# Sheet2.net
KiCad netlist of a schematic drawn in Altium Designer
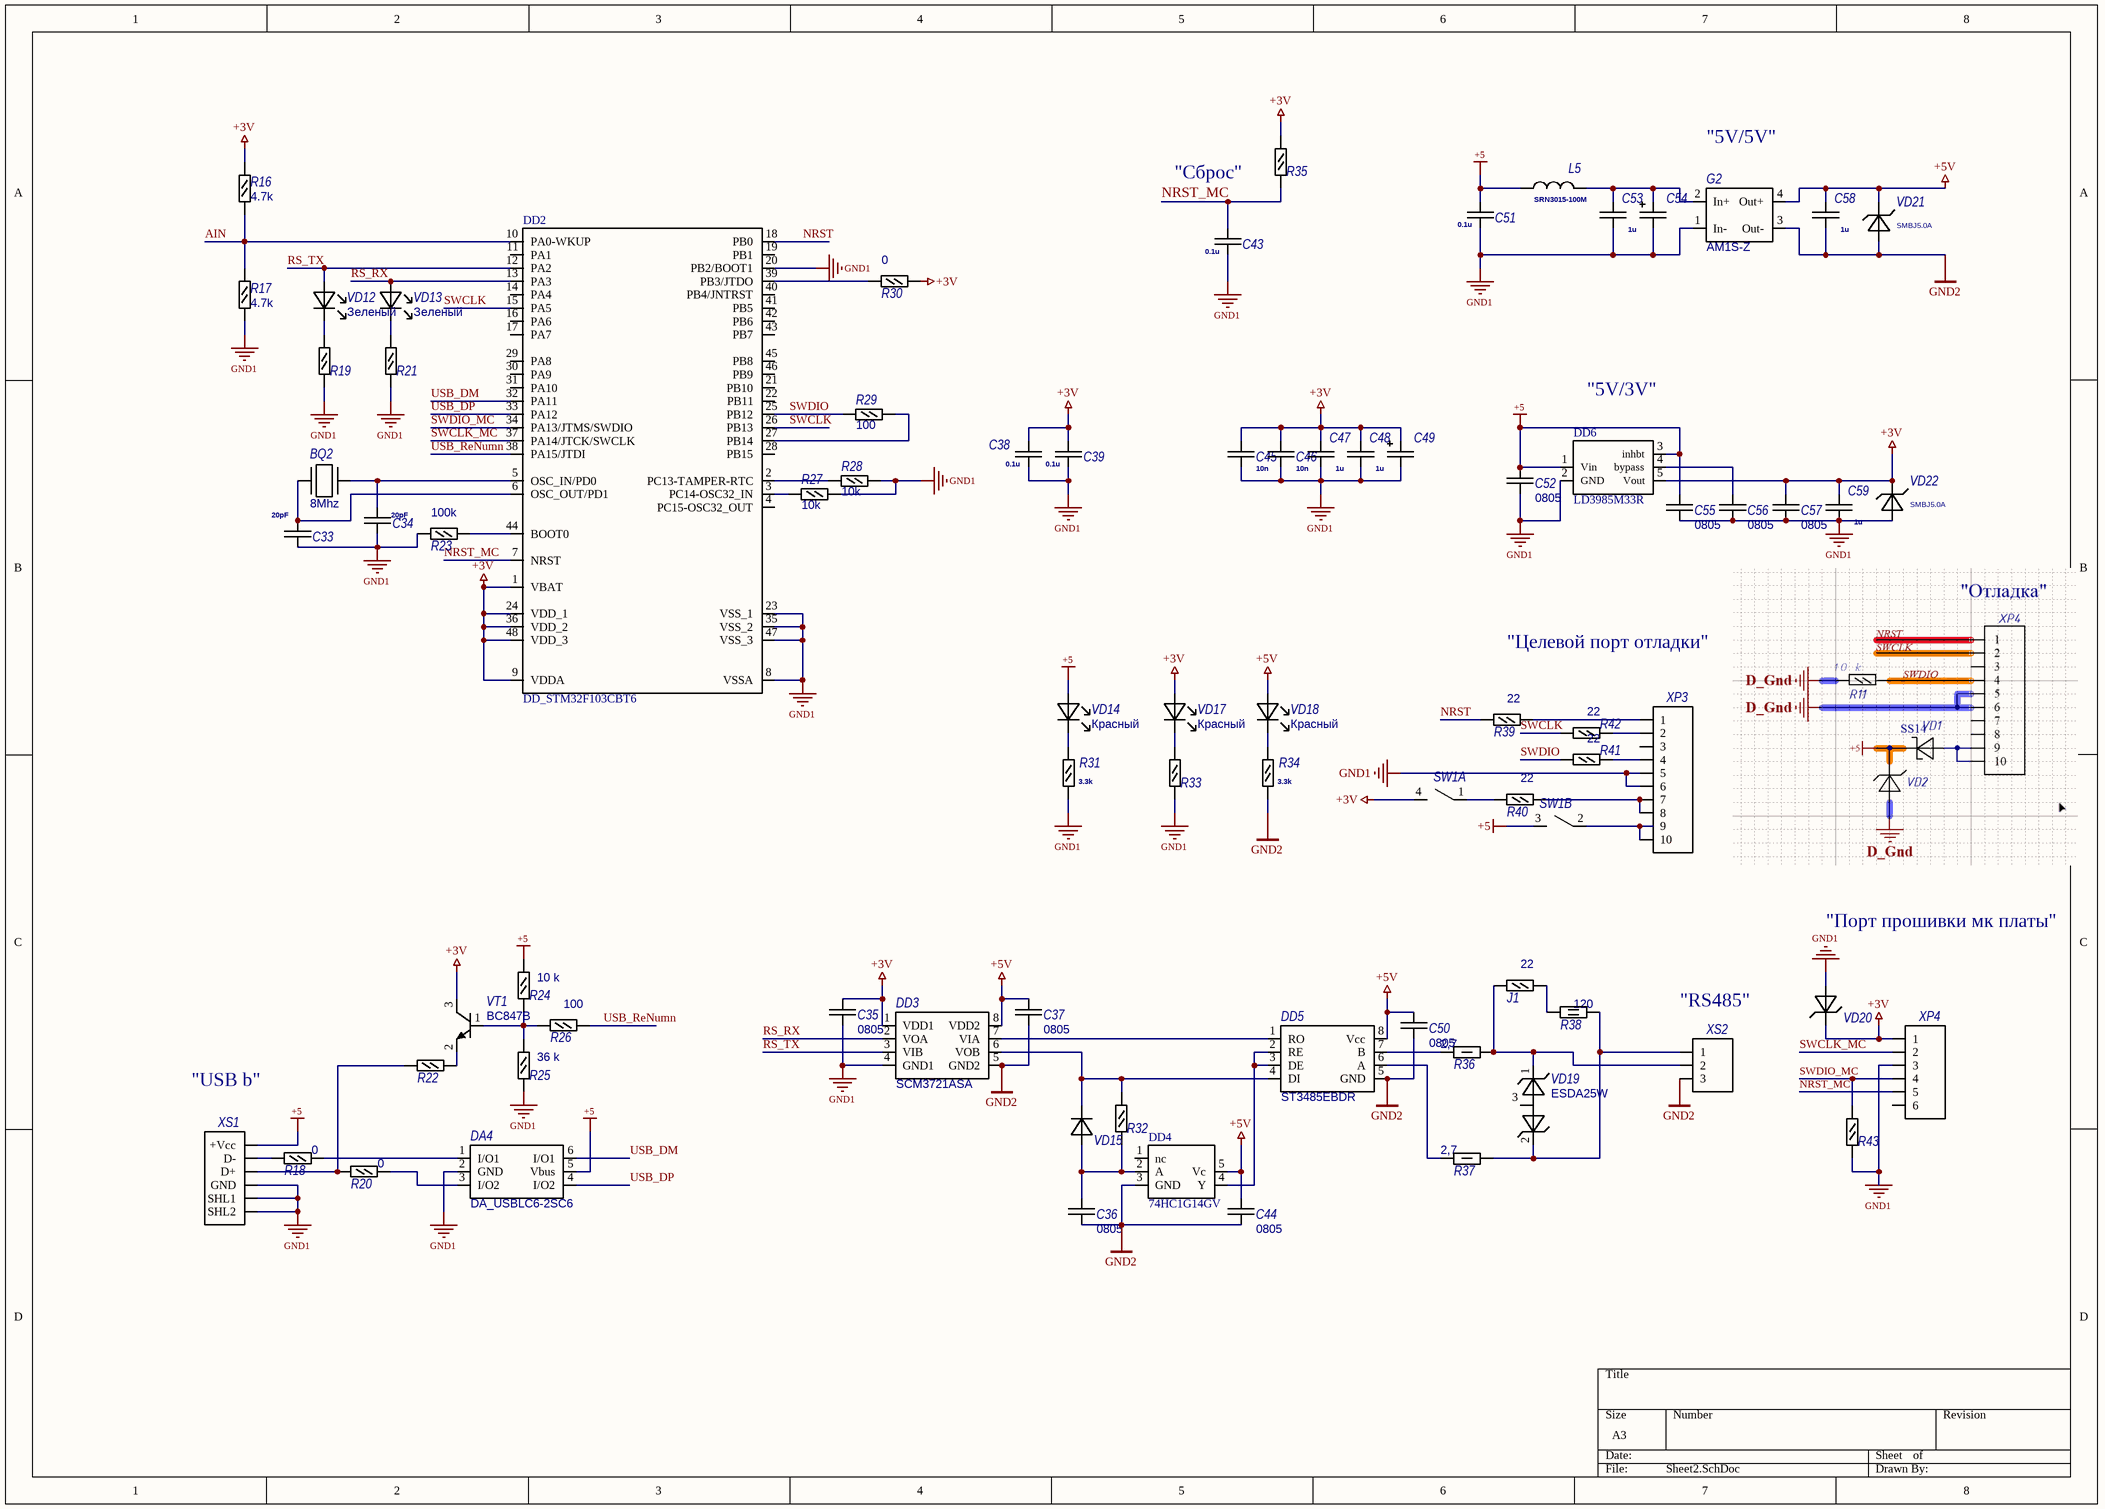
[diagram p0: Sheet2.SchDoc]

(export (version "E")
  (design (tool "Eeschema 10.0.6"))
  (components
    (comp (ref "BQ2") (value "8Mhz") (footprint "Xtal") (libsource (lib "Privod_A_K") (part "Xtal")))
    (comp (ref "C33")
      (value "~")
      (footprint "CAP_0805_(2x1.25x1.3)")
      (description "Керамика")
      (fields (field (name "НОМИНАЛ") "20pF"))
      (libsource (lib "Privod_A_K") (part "C_0805"))
    )
    (comp (ref "C34")
      (value "~")
      (footprint "CAP_0805_(2x1.25x1.3)")
      (description "Керамика")
      (fields (field (name "НОМИНАЛ") "20pF"))
      (libsource (lib "Privod_A_K") (part "C_0805"))
    )
    (comp (ref "C35")
      (value "0805")
      (footprint "CAP_0805_(2x1.25x1.3)")
      (description "Керамика")
      (libsource (lib "Privod_A_K") (part "C_0805"))
    )
    (comp (ref "C36")
      (value "0805")
      (footprint "CAP_0805_(2x1.25x1.3)")
      (description "Керамика")
      (libsource (lib "Privod_A_K") (part "C_0805"))
    )
    (comp (ref "C37")
      (value "0805")
      (footprint "CAP_0805_(2x1.25x1.3)")
      (description "Керамика")
      (libsource (lib "Privod_A_K") (part "C_0805"))
    )
    (comp (ref "C38")
      (value "0.1u")
      (footprint "CAP_0805_(2x1.25x1.3)")
      (description "Керамика")
      (libsource (lib "Privod_A_K") (part "C_0805"))
    )
    (comp (ref "C39")
      (value "0.1u")
      (footprint "CAP_0805_(2x1.25x1.3)")
      (description "Керамика")
      (libsource (lib "Privod_A_K") (part "C_0805"))
    )
    (comp (ref "C43")
      (value "0.1u")
      (footprint "CAP_0805_(2x1.25x1.3)")
      (description "Керамика")
      (libsource (lib "Privod_A_K") (part "C_0805"))
    )
    (comp (ref "C44")
      (value "0805")
      (footprint "CAP_0805_(2x1.25x1.3)")
      (description "Керамика")
      (libsource (lib "Privod_A_K") (part "C_0805"))
    )
    (comp (ref "C45")
      (value "10n")
      (footprint "CAP_0805_(2x1.25x1.3)")
      (description "Керамика")
      (libsource (lib "Privod_A_K") (part "C_0805"))
    )
    (comp (ref "C46")
      (value "10n")
      (footprint "CAP_0805_(2x1.25x1.3)")
      (description "Керамика")
      (libsource (lib "Privod_A_K") (part "C_0805"))
    )
    (comp (ref "C47")
      (value "1u")
      (footprint "CAP_0805_(2x1.25x1.3)")
      (description "Керамика")
      (libsource (lib "Privod_A_K") (part "C_0805"))
    )
    (comp (ref "C48")
      (value "1u")
      (footprint "CAP_0805_(2x1.25x1.3)")
      (description "Керамика")
      (libsource (lib "Privod_A_K") (part "C_0805"))
    )
    (comp (ref "C49")
      (value "TAN_A")
      (footprint "CAP_TAN_B")
      (description "Capacitor")
      (libsource (lib "Privod_A_K") (part "C+_TAN_B"))
    )
    (comp (ref "C50")
      (value "0805")
      (footprint "CAP_0805_(2x1.25x1.3)")
      (description "Керамика")
      (libsource (lib "Privod_A_K") (part "C_0805"))
    )
    (comp (ref "C51")
      (value "0.1u")
      (footprint "CAP_0805_(2x1.25x1.3)")
      (description "Керамика")
      (libsource (lib "Privod_A_K") (part "C_0805"))
    )
    (comp (ref "C52")
      (value "0805")
      (footprint "CAP_0805_(2x1.25x1.3)")
      (description "Керамика")
      (libsource (lib "Privod_A_K") (part "C_0805"))
    )
    (comp (ref "C53")
      (value "1u")
      (footprint "CAP_0805_(2x1.25x1.3)")
      (description "Керамика")
      (libsource (lib "Privod_A_K") (part "C_0805"))
    )
    (comp (ref "C54")
      (value "TAN_A")
      (footprint "CAP_TAN_B")
      (description "Capacitor")
      (libsource (lib "Privod_A_K") (part "C+_TAN_B"))
    )
    (comp (ref "C55")
      (value "0805")
      (footprint "CAP_0805_(2x1.25x1.3)")
      (description "Керамика")
      (libsource (lib "Privod_A_K") (part "C_0805"))
    )
    (comp (ref "C56")
      (value "0805")
      (footprint "CAP_0805_(2x1.25x1.3)")
      (description "Керамика")
      (libsource (lib "Privod_A_K") (part "C_0805"))
    )
    (comp (ref "C57")
      (value "0805")
      (footprint "CAP_0805_(2x1.25x1.3)")
      (description "Керамика")
      (libsource (lib "Privod_A_K") (part "C_0805"))
    )
    (comp (ref "C58")
      (value "1u")
      (footprint "CAP_0805_(2x1.25x1.3)")
      (description "Керамика")
      (libsource (lib "Privod_A_K") (part "C_0805"))
    )
    (comp (ref "C59")
      (value "1u")
      (footprint "CAP_0805_(2x1.25x1.3)")
      (description "Керамика")
      (libsource (lib "Privod_A_K") (part "C_0805"))
    )
    (comp (ref "DA4")
      (value "DA_USBLC6-2SC6")
      (footprint "SOT-23-6L")
      (description "USB ESD protector SOT23-6")
      (libsource (lib "Privod_A_K") (part "DA_USBLC6-2SC6"))
    )
    (comp (ref "DD2")
      (value "DD_STM32F103CBT6")
      (footprint "LQFP_48")
      (description "STM32 ARM-based 32-bit MCU with 128 Kbytes Flash, 48-pin LQFP, Industrial Temperature")
      (fields (field (name "PUBLISHER") "Altium Limited"))
      (libsource (lib "Privod_A_K") (part "DD_STM32F103CBT6"))
    )
    (comp (ref "DD3")
      (value "SCM3721ASA")
      (footprint "SOP-8")
      (description "Dual-ChannelDigital Isolators")
      (libsource (lib "Privod_A_K") (part "DD_SCM3721ASA"))
    )
    (comp (ref "DD4")
      (value "74HC1G14GV")
      (footprint "sot-23-5")
      (description "1 канал инвертирующ триггер шмитта")
      (libsource (lib "Privod_A_K") (part "DD_74HC1G14GV"))
    )
    (comp (ref "DD5")
      (value "ST3485EBDR")
      (footprint "SO-8_(0.15')")
      (description "RS485/422 Приемопередатчик интерфейса")
      (libsource (lib "Privod_A_K") (part "DD_ST3485EBDR"))
    )
    (comp (ref "DD6")
      (value "LD3985M33R")
      (footprint "sot-23-5")
      (description "Источник опорного напряжения 3.3В")
      (libsource (lib "Privod_A_K") (part "DD_LD3985M33R"))
    )
    (comp (ref "G2")
      (value "AM1S-Z")
      (footprint "AM1S-Z")
      (description "DC/DC")
      (libsource (lib "Privod_A_K") (part "G_AM1S-Z"))
    )
    (comp (ref "J1")
      (value "0805")
      (footprint "RES_0805_(2x1.2x0.45)_0.125Вт")
      (description "Resistor")
      (fields (field (name "НОМИНАЛ") "22"))
      (libsource (lib "") (part "R_0805_2"))
    )
    (comp (ref "L5")
      (value "SRN3015-100M")
      (footprint "L_SRN3015")
      (description "L")
      (libsource (lib "Privod_A_K") (part "L_SRN3015"))
    )
    (comp (ref "R16")
      (value "0805")
      (footprint "RES_0805_(2x1.2x0.45)_0.125Вт")
      (description "Resistor")
      (fields (field (name "НОМИНАЛ") "4.7k"))
      (libsource (lib "") (part "R_0805_1"))
    )
    (comp (ref "R17")
      (value "0805")
      (footprint "RES_0805_(2x1.2x0.45)_0.125Вт")
      (description "Resistor")
      (fields (field (name "НОМИНАЛ") "4.7k"))
      (libsource (lib "") (part "R_0805_1"))
    )
    (comp (ref "R18")
      (value "0805")
      (footprint "RES_0805_(2x1.2x0.45)_0.125Вт")
      (description "Resistor")
      (fields (field (name "НОМИНАЛ") "0"))
      (libsource (lib "") (part "R_0805_2"))
    )
    (comp (ref "R19")
      (value "0805")
      (footprint "RES_0805_(2x1.2x0.45)_0.125Вт")
      (description "Resistor")
      (libsource (lib "") (part "R_0805_1"))
    )
    (comp (ref "R20")
      (value "0805")
      (footprint "RES_0805_(2x1.2x0.45)_0.125Вт")
      (description "Resistor")
      (fields (field (name "НОМИНАЛ") "0"))
      (libsource (lib "") (part "R_0805_2"))
    )
    (comp (ref "R21")
      (value "0805")
      (footprint "RES_0805_(2x1.2x0.45)_0.125Вт")
      (description "Resistor")
      (libsource (lib "") (part "R_0805_1"))
    )
    (comp (ref "R22")
      (value "0805")
      (footprint "RES_0805_(2x1.2x0.45)_0.125Вт")
      (description "Resistor")
      (libsource (lib "") (part "R_0805_2"))
    )
    (comp (ref "R23")
      (value "0805")
      (footprint "RES_0805_(2x1.2x0.45)_0.125Вт")
      (description "Resistor")
      (fields (field (name "НОМИНАЛ") "100k"))
      (libsource (lib "") (part "R_0805_2"))
    )
    (comp (ref "R24")
      (value "0805")
      (footprint "RES_0805_(2x1.2x0.45)_0.125Вт")
      (description "Resistor")
      (fields (field (name "НОМИНАЛ") "10 k"))
      (libsource (lib "") (part "R_0805_1"))
    )
    (comp (ref "R25")
      (value "0805")
      (footprint "RES_0805_(2x1.2x0.45)_0.125Вт")
      (description "Resistor")
      (fields (field (name "НОМИНАЛ") "36 k"))
      (libsource (lib "") (part "R_0805_1"))
    )
    (comp (ref "R26")
      (value "0805")
      (footprint "RES_0805_(2x1.2x0.45)_0.125Вт")
      (description "Resistor")
      (fields (field (name "НОМИНАЛ") "100"))
      (libsource (lib "") (part "R_0805_2"))
    )
    (comp (ref "R27")
      (value "0805")
      (footprint "RES_0805_(2x1.2x0.45)_0.125Вт")
      (description "Resistor")
      (fields (field (name "НОМИНАЛ") "10k"))
      (libsource (lib "Privod_A_K") (part "R_0805"))
    )
    (comp (ref "R28")
      (value "0805")
      (footprint "RES_0805_(2x1.2x0.45)_0.125Вт")
      (description "Resistor")
      (fields (field (name "НОМИНАЛ") "10k"))
      (libsource (lib "Privod_A_K") (part "R_0805"))
    )
    (comp (ref "R29")
      (value "0805")
      (footprint "RES_0805_(2x1.2x0.45)_0.125Вт")
      (description "Resistor")
      (fields (field (name "НОМИНАЛ") "100"))
      (libsource (lib "Privod_A_K") (part "R_0805"))
    )
    (comp (ref "R30")
      (value "0805")
      (footprint "RES_0805_(2x1.2x0.45)_0.125Вт")
      (description "Resistor")
      (fields (field (name "НОМИНАЛ") "0"))
      (libsource (lib "") (part "R_0805_2"))
    )
    (comp (ref "R31")
      (value "3.3k")
      (footprint "RES_0805_(2x1.2x0.45)_0.125Вт")
      (description "Resistor")
      (libsource (lib "") (part "R_0805_1"))
    )
    (comp (ref "R32")
      (value "0805")
      (footprint "RES_0805_(2x1.2x0.45)_0.125Вт")
      (description "Resistor")
      (libsource (lib "") (part "R_0805_3"))
    )
    (comp (ref "R33")
      (value "0805")
      (footprint "RES_0805_(2x1.2x0.45)_0.125Вт")
      (description "Resistor")
      (libsource (lib "") (part "R_0805_1"))
    )
    (comp (ref "R34")
      (value "3.3k")
      (footprint "RES_0805_(2x1.2x0.45)_0.125Вт")
      (description "Resistor")
      (libsource (lib "") (part "R_0805_1"))
    )
    (comp (ref "R35")
      (value "0805")
      (footprint "RES_0805_(2x1.2x0.45)_0.125Вт")
      (description "Resistor")
      (libsource (lib "") (part "R_0805_3"))
    )
    (comp (ref "R36")
      (value "1210")
      (footprint "RES_1210_(3.2x2.5x0.55)_0.5Вт")
      (description "Resistor")
      (fields (field (name "НОМИНАЛ") "2,7"))
      (libsource (lib "Privod_A_K") (part "R_1210"))
    )
    (comp (ref "R37")
      (value "1210")
      (footprint "RES_1210_(3.2x2.5x0.55)_0.5Вт")
      (description "Resistor")
      (fields (field (name "НОМИНАЛ") "2,7"))
      (libsource (lib "Privod_A_K") (part "R_1210"))
    )
    (comp (ref "R38")
      (value "2512")
      (footprint "RES_2512_(6.3x3.1x0.6)_2Вт")
      (fields (field (name "НОМИНАЛ") "120"))
      (libsource (lib "Privod_A_K") (part "R_2512"))
    )
    (comp (ref "R39")
      (value "0805")
      (footprint "RES_0805_(2x1.2x0.45)_0.125Вт")
      (description "Resistor")
      (fields (field (name "НОМИНАЛ") "22"))
      (libsource (lib "") (part "R_0805_2"))
    )
    (comp (ref "R40")
      (value "0805")
      (footprint "RES_0805_(2x1.2x0.45)_0.125Вт")
      (description "Resistor")
      (fields (field (name "НОМИНАЛ") "22"))
      (libsource (lib "") (part "R_0805_2"))
    )
    (comp (ref "R41")
      (value "0805")
      (footprint "RES_0805_(2x1.2x0.45)_0.125Вт")
      (description "Resistor")
      (fields (field (name "НОМИНАЛ") "22"))
      (libsource (lib "") (part "R_0805_2"))
    )
    (comp (ref "R42")
      (value "0805")
      (footprint "RES_0805_(2x1.2x0.45)_0.125Вт")
      (description "Resistor")
      (fields (field (name "НОМИНАЛ") "22"))
      (libsource (lib "") (part "R_0805_2"))
    )
    (comp (ref "R43")
      (value "0805")
      (footprint "RES_0805_(2x1.2x0.45)_0.125Вт")
      (description "Resistor")
      (libsource (lib "") (part "R_0805_3"))
    )
    (comp (ref "SW1")
      (value "SW_2_pin")
      (footprint "SW_DS1040_2pin")
      (libsource (lib "Privod_A_K") (part "SW_2_pin"))
    )
    (comp (ref "VD12")
      (value "VD_Led_0805")
      (footprint "led_0805")
      (fields (field (name "ПРИМЕЧАНИЯ") "Зеленый"))
      (libsource (lib "Privod_A_K") (part "VD_Led_0805"))
    )
    (comp (ref "VD13")
      (value "VD_Led_0805")
      (footprint "led_0805")
      (fields (field (name "ПРИМЕЧАНИЯ") "Зеленый"))
      (libsource (lib "Privod_A_K") (part "VD_Led_0805"))
    )
    (comp (ref "VD14")
      (value "VD_Led_0805")
      (footprint "led_0805")
      (fields (field (name "ПРИМЕЧАНИЯ") "Красный"))
      (libsource (lib "Privod_A_K") (part "VD_Led_0805"))
    )
    (comp (ref "VD15")
      (value "VD")
      (footprint "VD_SMA_(Do-214AC)")
      (description "Diode")
      (libsource (lib "Privod_A_K") (part "VD"))
    )
    (comp (ref "VD17")
      (value "VD_Led_0805")
      (footprint "led_0805")
      (fields (field (name "ПРИМЕЧАНИЯ") "Красный"))
      (libsource (lib "Privod_A_K") (part "VD_Led_0805"))
    )
    (comp (ref "VD18")
      (value "VD_Led_0805")
      (footprint "led_0805")
      (fields (field (name "ПРИМЕЧАНИЯ") "Красный"))
      (libsource (lib "Privod_A_K") (part "VD_Led_0805"))
    )
    (comp (ref "VD19")
      (value "ESDA25W")
      (footprint "SOT-323-3L")
      (description "Защитный биполярный диод")
      (libsource (lib "Privod_A_K") (part "VD_ESDA25W"))
    )
    (comp (ref "VD20")
      (value "ESD")
      (footprint "VD_SOD523")
      (description "Защитный диод")
      (libsource (lib "Privod_A_K") (part "VD_ESD"))
    )
    (comp (ref "VD21")
      (value "SMBJ5.0A")
      (footprint "VD_SMB_(Do-214AA)")
      (description "Защитный диод 600W 5V 5% [SMB]")
      (libsource (lib "Privod_A_K") (part "VD_SMBJ50A"))
    )
    (comp (ref "VD22")
      (value "SMBJ5.0A")
      (footprint "VD_SMB_(Do-214AA)")
      (description "Защитный диод 600W 5V 5% [SMB]")
      (libsource (lib "Privod_A_K") (part "VD_SMBJ50A"))
    )
    (comp (ref "VT1")
      (value "BC847B")
      (footprint "SOT-23")
      (description "NPN Bipolar Transistor")
      (libsource (lib "Privod_A_K") (part "VT_BC847B"))
    )
    (comp (ref "XP3")
      (value "XP_5x2_H")
      (footprint "XP_5x2_PIN_H")
      (libsource (lib "Privod_A_K") (part "XP_5x2_H"))
    )
    (comp (ref "XP4")
      (value "XP_6_pin")
      (footprint "XP_6_Pin")
      (libsource (lib "Privod_A_K") (part "XP_6_pin"))
    )
    (comp (ref "XS1")
      (value "XS_USB_B")
      (footprint "XS_USBB")
      (libsource (lib "Privod_A_K") (part "XS_USB_B"))
    )
    (comp (ref "XS2")
      (value "XS_3_pin_2.54")
      (footprint "XS_KLS-2.54-03P")
      (libsource (lib "Privod_A_K") (part "XS_3_pin_2.54"))
    )
  )
  (nets
    (net (code "1") (name "+3V") (class "Default")
      (node (ref "C35") (pin "2") (pinfunction "2_2") (pintype "passive"))
      (node (ref "C38") (pin "2") (pinfunction "2_2") (pintype "passive"))
      (node (ref "C39") (pin "2") (pinfunction "2_2") (pintype "passive"))
      (node (ref "C45") (pin "1") (pinfunction "1_1") (pintype "passive"))
      (node (ref "C46") (pin "1") (pinfunction "1_1") (pintype "passive"))
      (node (ref "C47") (pin "1") (pinfunction "1_1") (pintype "passive"))
      (node (ref "C48") (pin "1") (pinfunction "1_1") (pintype "passive"))
      (node (ref "C49") (pin "1") (pinfunction "1_1") (pintype "passive"))
      (node (ref "C57") (pin "2") (pinfunction "2_2") (pintype "passive"))
      (node (ref "C59") (pin "1") (pinfunction "1_1") (pintype "passive"))
      (node (ref "DD2") (pin "1") (pinfunction "VBAT_1") (pintype "passive"))
      (node (ref "DD2") (pin "24") (pinfunction "VDD_1_24") (pintype "passive"))
      (node (ref "DD2") (pin "36") (pinfunction "VDD_2_36") (pintype "passive"))
      (node (ref "DD2") (pin "48") (pinfunction "VDD_3_48") (pintype "passive"))
      (node (ref "DD2") (pin "9") (pinfunction "VDDA_9") (pintype "passive"))
      (node (ref "DD3") (pin "1") (pinfunction "VDD1_1") (pintype "passive"))
      (node (ref "DD6") (pin "5") (pinfunction "Vout_5") (pintype "passive"))
      (node (ref "R16") (pin "2") (pinfunction "2_2") (pintype "passive"))
      (node (ref "R30") (pin "1") (pinfunction "1_1") (pintype "passive"))
      (node (ref "R35") (pin "1") (pinfunction "1_1") (pintype "passive"))
      (node (ref "SW1") (pin "4") (pinfunction "4_4") (pintype "passive"))
      (node (ref "VD17") (pin "1") (pinfunction "A_1") (pintype "passive"))
      (node (ref "VD20") (pin "2") (pinfunction "K_2") (pintype "passive"))
      (node (ref "VD22") (pin "2") (pinfunction "K_2") (pintype "passive"))
      (node (ref "VT1") (pin "3") (pinfunction "C_3") (pintype "passive"))
      (node (ref "XP4") (pin "1") (pinfunction "1_1") (pintype "passive"))
    )
    (net (code "2") (name "+5") (class "Default")
      (node (ref "C51") (pin "2") (pinfunction "2_2") (pintype "passive"))
      (node (ref "C52") (pin "2") (pinfunction "2_2") (pintype "passive"))
      (node (ref "C55") (pin "2") (pinfunction "2_2") (pintype "passive"))
      (node (ref "DA4") (pin "5") (pinfunction "Vbus_5") (pintype "passive"))
      (node (ref "DD6") (pin "1") (pinfunction "Vin_1") (pintype "passive"))
      (node (ref "DD6") (pin "3") (pinfunction "inhbt_3") (pintype "passive"))
      (node (ref "L5") (pin "1") (pinfunction "1_1") (pintype "passive"))
      (node (ref "R24") (pin "2") (pinfunction "2_2") (pintype "passive"))
      (node (ref "SW1") (pin "3") (pinfunction "3_3") (pintype "passive"))
      (node (ref "VD14") (pin "1") (pinfunction "A_1") (pintype "passive"))
      (node (ref "XS1") (pin "1") (pinfunction "+Vcc_1") (pintype "passive"))
    )
    (net (code "3") (name "+5V") (class "Default")
      (node (ref "C37") (pin "2") (pinfunction "2_2") (pintype "passive"))
      (node (ref "C44") (pin "2") (pinfunction "2_2") (pintype "passive"))
      (node (ref "C50") (pin "2") (pinfunction "2_2") (pintype "passive"))
      (node (ref "C58") (pin "1") (pinfunction "1_1") (pintype "passive"))
      (node (ref "DD3") (pin "8") (pinfunction "VDD2_8") (pintype "passive"))
      (node (ref "DD4") (pin "5") (pinfunction "Vc_5") (pintype "passive"))
      (node (ref "DD5") (pin "8") (pinfunction "Vcc_8") (pintype "passive"))
      (node (ref "G2") (pin "4") (pinfunction "Out+_4") (pintype "passive"))
      (node (ref "VD18") (pin "1") (pinfunction "A_1") (pintype "passive"))
      (node (ref "VD21") (pin "2") (pinfunction "K_2") (pintype "passive"))
    )
    (net (code "4") (name "/AIN") (class "Default")
      (node (ref "DD2") (pin "10") (pinfunction "PA0-WKUP_10") (pintype "passive"))
      (node (ref "R16") (pin "1") (pinfunction "1_1") (pintype "passive"))
      (node (ref "R17") (pin "2") (pinfunction "2_2") (pintype "passive"))
    )
    (net (code "5") (name "/NRST") (class "Default")
      (node (ref "DD2") (pin "18") (pinfunction "PB0_18") (pintype "passive"))
      (node (ref "R39") (pin "2") (pinfunction "2_2") (pintype "passive"))
    )
    (net (code "6") (name "/NRST_MC") (class "Default")
      (node (ref "C43") (pin "2") (pinfunction "2_2") (pintype "passive"))
      (node (ref "DD2") (pin "7") (pinfunction "NRST_7") (pintype "passive"))
      (node (ref "R35") (pin "2") (pinfunction "2_2") (pintype "passive"))
      (node (ref "XP4") (pin "5") (pinfunction "5_5") (pintype "passive"))
    )
    (net (code "7") (name "/RS_RX") (class "Default")
      (node (ref "DD2") (pin "13") (pinfunction "PA3_13") (pintype "passive"))
      (node (ref "DD3") (pin "2") (pinfunction "VOA_2") (pintype "passive"))
      (node (ref "VD13") (pin "1") (pinfunction "A_1") (pintype "passive"))
    )
    (net (code "8") (name "/RS_TX") (class "Default")
      (node (ref "DD2") (pin "12") (pinfunction "PA2_12") (pintype "passive"))
      (node (ref "DD3") (pin "3") (pinfunction "VIB_3") (pintype "passive"))
      (node (ref "VD12") (pin "1") (pinfunction "A_1") (pintype "passive"))
    )
    (net (code "9") (name "/SWCLK") (class "Default")
      (node (ref "DD2") (pin "15") (pinfunction "PA5_15") (pintype "passive"))
      (node (ref "DD2") (pin "26") (pinfunction "PB13_26") (pintype "passive"))
      (node (ref "R42") (pin "2") (pinfunction "2_2") (pintype "passive"))
    )
    (net (code "10") (name "/SWCLK_MC") (class "Default")
      (node (ref "DD2") (pin "37") (pinfunction "PA14/JTCK/SWCLK_37") (pintype "passive"))
      (node (ref "XP4") (pin "2") (pinfunction "2_2") (pintype "passive"))
    )
    (net (code "11") (name "/SWDIO") (class "Default")
      (node (ref "DD2") (pin "25") (pinfunction "PB12_25") (pintype "passive"))
      (node (ref "R29") (pin "1") (pinfunction "1_1") (pintype "passive"))
      (node (ref "R41") (pin "2") (pinfunction "2_2") (pintype "passive"))
    )
    (net (code "12") (name "/SWDIO_MC") (class "Default")
      (node (ref "DD2") (pin "34") (pinfunction "PA13/JTMS/SWDIO_34") (pintype "passive"))
      (node (ref "R43") (pin "1") (pinfunction "1_1") (pintype "passive"))
      (node (ref "XP4") (pin "4") (pinfunction "4_4") (pintype "passive"))
    )
    (net (code "13") (name "/USB_DM") (class "Default")
      (node (ref "DA4") (pin "6") (pinfunction "I/O1_6") (pintype "passive"))
      (node (ref "DD2") (pin "32") (pinfunction "PA11_32") (pintype "passive"))
    )
    (net (code "14") (name "/USB_DP") (class "Default")
      (node (ref "DA4") (pin "4") (pinfunction "I/O2_4") (pintype "passive"))
      (node (ref "DD2") (pin "33") (pinfunction "PA12_33") (pintype "passive"))
    )
    (net (code "15") (name "/USB_ReNumn") (class "Default")
      (node (ref "DD2") (pin "38") (pinfunction "PA15/JTDI_38") (pintype "passive"))
      (node (ref "R26") (pin "1") (pinfunction "1_1") (pintype "passive"))
    )
    (net (code "16") (name "GND1") (class "Default")
      (node (ref "C33") (pin "1") (pinfunction "1_1") (pintype "passive"))
      (node (ref "C34") (pin "1") (pinfunction "1_1") (pintype "passive"))
      (node (ref "C35") (pin "1") (pinfunction "1_1") (pintype "passive"))
      (node (ref "C38") (pin "1") (pinfunction "1_1") (pintype "passive"))
      (node (ref "C39") (pin "1") (pinfunction "1_1") (pintype "passive"))
      (node (ref "C43") (pin "1") (pinfunction "1_1") (pintype "passive"))
      (node (ref "C45") (pin "2") (pinfunction "2_2") (pintype "passive"))
      (node (ref "C46") (pin "2") (pinfunction "2_2") (pintype "passive"))
      (node (ref "C47") (pin "2") (pinfunction "2_2") (pintype "passive"))
      (node (ref "C48") (pin "2") (pinfunction "2_2") (pintype "passive"))
      (node (ref "C49") (pin "2") (pinfunction "2_2") (pintype "passive"))
      (node (ref "C51") (pin "1") (pinfunction "1_1") (pintype "passive"))
      (node (ref "C52") (pin "1") (pinfunction "1_1") (pintype "passive"))
      (node (ref "C53") (pin "2") (pinfunction "2_2") (pintype "passive"))
      (node (ref "C54") (pin "2") (pinfunction "2_2") (pintype "passive"))
      (node (ref "C55") (pin "1") (pinfunction "1_1") (pintype "passive"))
      (node (ref "C56") (pin "1") (pinfunction "1_1") (pintype "passive"))
      (node (ref "C57") (pin "1") (pinfunction "1_1") (pintype "passive"))
      (node (ref "C59") (pin "2") (pinfunction "2_2") (pintype "passive"))
      (node (ref "DA4") (pin "2") (pinfunction "GND_2") (pintype "passive"))
      (node (ref "DD2") (pin "20") (pinfunction "PB2/BOOT1_20") (pintype "passive"))
      (node (ref "DD2") (pin "23") (pinfunction "VSS_1_23") (pintype "passive"))
      (node (ref "DD2") (pin "35") (pinfunction "VSS_2_35") (pintype "passive"))
      (node (ref "DD2") (pin "47") (pinfunction "VSS_3_47") (pintype "passive"))
      (node (ref "DD2") (pin "8") (pinfunction "VSSA_8") (pintype "passive"))
      (node (ref "DD3") (pin "4") (pinfunction "GND1_4") (pintype "passive"))
      (node (ref "DD6") (pin "2") (pinfunction "GND_2") (pintype "passive"))
      (node (ref "G2") (pin "1") (pinfunction "In-_1") (pintype "passive"))
      (node (ref "R17") (pin "1") (pinfunction "1_1") (pintype "passive"))
      (node (ref "R19") (pin "1") (pinfunction "1_1") (pintype "passive"))
      (node (ref "R21") (pin "1") (pinfunction "1_1") (pintype "passive"))
      (node (ref "R23") (pin "2") (pinfunction "2_2") (pintype "passive"))
      (node (ref "R25") (pin "1") (pinfunction "1_1") (pintype "passive"))
      (node (ref "R27") (pin "2") (pinfunction "2_2") (pintype "passive"))
      (node (ref "R28") (pin "2") (pinfunction "2_2") (pintype "passive"))
      (node (ref "R31") (pin "1") (pinfunction "1_1") (pintype "passive"))
      (node (ref "R33") (pin "1") (pinfunction "1_1") (pintype "passive"))
      (node (ref "R43") (pin "2") (pinfunction "2_2") (pintype "passive"))
      (node (ref "VD20") (pin "1") (pinfunction "A_1") (pintype "passive"))
      (node (ref "VD22") (pin "1") (pinfunction "A_1") (pintype "passive"))
      (node (ref "XP3") (pin "5") (pinfunction "5_5") (pintype "passive"))
      (node (ref "XP3") (pin "6") (pinfunction "6_6") (pintype "passive"))
      (node (ref "XP4") (pin "3") (pinfunction "3_3") (pintype "passive"))
      (node (ref "XS1") (pin "4") (pinfunction "GND_4") (pintype "passive"))
      (node (ref "XS1") (pin "5") (pinfunction "SHL1_5") (pintype "passive"))
      (node (ref "XS1") (pin "6") (pinfunction "SHL2_6") (pintype "passive"))
    )
    (net (code "17") (name "GND2") (class "Default")
      (node (ref "C36") (pin "1") (pinfunction "1_1") (pintype "passive"))
      (node (ref "C37") (pin "1") (pinfunction "1_1") (pintype "passive"))
      (node (ref "C44") (pin "1") (pinfunction "1_1") (pintype "passive"))
      (node (ref "C50") (pin "1") (pinfunction "1_1") (pintype "passive"))
      (node (ref "C58") (pin "2") (pinfunction "2_2") (pintype "passive"))
      (node (ref "DD3") (pin "5") (pinfunction "GND2_5") (pintype "passive"))
      (node (ref "DD4") (pin "3") (pinfunction "GND_3") (pintype "passive"))
      (node (ref "DD5") (pin "5") (pinfunction "GND_5") (pintype "passive"))
      (node (ref "G2") (pin "3") (pinfunction "Out-_3") (pintype "passive"))
      (node (ref "R34") (pin "1") (pinfunction "1_1") (pintype "passive"))
      (node (ref "VD21") (pin "1") (pinfunction "A_1") (pintype "passive"))
      (node (ref "XS2") (pin "3") (pinfunction "3_3") (pintype "passive"))
    )
    (net (code "18") (name "Net-(DA4-I{slash}O1-Pad1)") (class "Default")
      (node (ref "DA4") (pin "1") (pinfunction "I/O1_1") (pintype "passive"))
      (node (ref "R18") (pin "1") (pinfunction "1_1") (pintype "passive"))
    )
    (net (code "19") (name "Net-(DA4-I{slash}O2-Pad3)") (class "Default")
      (node (ref "DA4") (pin "3") (pinfunction "I/O2_3") (pintype "passive"))
      (node (ref "R20") (pin "1") (pinfunction "1_1") (pintype "passive"))
    )
    (net (code "20") (name "Net-(DD2-BOOT0)") (class "Default")
      (node (ref "DD2") (pin "44") (pinfunction "BOOT0_44") (pintype "passive"))
      (node (ref "R23") (pin "1") (pinfunction "1_1") (pintype "passive"))
    )
    (net (code "21") (name "Net-(DD2-OSC_IN{slash}PD0)") (class "Default")
      (node (ref "BQ2") (pin "1") (pinfunction "1_1") (pintype "passive"))
      (node (ref "C34") (pin "2") (pinfunction "2_2") (pintype "passive"))
      (node (ref "DD2") (pin "5") (pinfunction "OSC_IN/PD0_5") (pintype "passive"))
    )
    (net (code "22") (name "Net-(DD2-OSC_OUT{slash}PD1)") (class "Default")
      (node (ref "BQ2") (pin "2") (pinfunction "2_2") (pintype "passive"))
      (node (ref "C33") (pin "2") (pinfunction "2_2") (pintype "passive"))
      (node (ref "DD2") (pin "6") (pinfunction "OSC_OUT/PD1_6") (pintype "passive"))
    )
    (net (code "23") (name "Net-(DD2-PB3{slash}JTDO)") (class "Default")
      (node (ref "DD2") (pin "39") (pinfunction "PB3/JTDO_39") (pintype "passive"))
      (node (ref "R30") (pin "2") (pinfunction "2_2") (pintype "passive"))
    )
    (net (code "24") (name "Net-(DD2-PB14)") (class "Default")
      (node (ref "DD2") (pin "27") (pinfunction "PB14_27") (pintype "passive"))
      (node (ref "R29") (pin "2") (pinfunction "2_2") (pintype "passive"))
    )
    (net (code "25") (name "Net-(DD2-PC13-TAMPER-RTC)") (class "Default")
      (node (ref "DD2") (pin "2") (pinfunction "PC13-TAMPER-RTC_2") (pintype "passive"))
      (node (ref "R28") (pin "1") (pinfunction "1_1") (pintype "passive"))
    )
    (net (code "26") (name "Net-(DD2-PC14-OSC32_IN)") (class "Default")
      (node (ref "DD2") (pin "3") (pinfunction "PC14-OSC32_IN_3") (pintype "passive"))
      (node (ref "R27") (pin "1") (pinfunction "1_1") (pintype "passive"))
    )
    (net (code "27") (name "Net-(DD3-VIA)") (class "Default")
      (node (ref "DD3") (pin "7") (pinfunction "VIA_7") (pintype "passive"))
      (node (ref "DD5") (pin "1") (pinfunction "RO_1") (pintype "passive"))
    )
    (net (code "28") (name "Net-(DD3-VOB)") (class "Default")
      (node (ref "DD3") (pin "6") (pinfunction "VOB_6") (pintype "passive"))
      (node (ref "DD5") (pin "4") (pinfunction "DI_4") (pintype "passive"))
      (node (ref "R32") (pin "1") (pinfunction "1_1") (pintype "passive"))
      (node (ref "VD15") (pin "2") (pinfunction "K_2") (pintype "passive"))
    )
    (net (code "29") (name "Net-(DD4-A)") (class "Default")
      (node (ref "C36") (pin "2") (pinfunction "2_2") (pintype "passive"))
      (node (ref "DD4") (pin "2") (pinfunction "A_2") (pintype "passive"))
      (node (ref "R32") (pin "2") (pinfunction "2_2") (pintype "passive"))
      (node (ref "VD15") (pin "1") (pinfunction "A_1") (pintype "passive"))
    )
    (net (code "30") (name "Net-(DD4-Y)") (class "Default")
      (node (ref "DD4") (pin "4") (pinfunction "Y_4") (pintype "passive"))
      (node (ref "DD5") (pin "2") (pinfunction "RE_2") (pintype "passive"))
      (node (ref "DD5") (pin "3") (pinfunction "DE_3") (pintype "passive"))
    )
    (net (code "31") (name "Net-(DD5-A)") (class "Default")
      (node (ref "DD5") (pin "6") (pinfunction "A_6") (pintype "passive"))
      (node (ref "R37") (pin "1") (pinfunction "1_1") (pintype "passive"))
    )
    (net (code "32") (name "Net-(DD5-B)") (class "Default")
      (node (ref "DD5") (pin "7") (pinfunction "B_7") (pintype "passive"))
      (node (ref "R36") (pin "1") (pinfunction "1_1") (pintype "passive"))
    )
    (net (code "33") (name "Net-(DD6-bypass)") (class "Default")
      (node (ref "C56") (pin "2") (pinfunction "2_2") (pintype "passive"))
      (node (ref "DD6") (pin "4") (pinfunction "bypass_4") (pintype "passive"))
    )
    (net (code "34") (name "Net-(G2-In+)") (class "Default")
      (node (ref "C53") (pin "1") (pinfunction "1_1") (pintype "passive"))
      (node (ref "C54") (pin "1") (pinfunction "1_1") (pintype "passive"))
      (node (ref "G2") (pin "2") (pinfunction "In+_2") (pintype "passive"))
      (node (ref "L5") (pin "2") (pinfunction "2_2") (pintype "passive"))
    )
    (net (code "35") (name "Net-(J1-Pad1)") (class "Default")
      (node (ref "J1") (pin "1") (pinfunction "1_1") (pintype "passive"))
      (node (ref "R38") (pin "1") (pinfunction "1_1") (pintype "passive"))
    )
    (net (code "36") (name "Net-(J1-Pad2)") (class "Default")
      (node (ref "J1") (pin "2") (pinfunction "2_2") (pintype "passive"))
      (node (ref "R36") (pin "2") (pinfunction "2_2") (pintype "passive"))
      (node (ref "VD19") (pin "1") (pinfunction "1_1") (pintype "passive"))
      (node (ref "XS2") (pin "2") (pinfunction "2_2") (pintype "passive"))
    )
    (net (code "37") (name "Net-(R37-Pad2)") (class "Default")
      (node (ref "R37") (pin "2") (pinfunction "2_2") (pintype "passive"))
      (node (ref "R38") (pin "2") (pinfunction "2_2") (pintype "passive"))
      (node (ref "VD19") (pin "2") (pinfunction "2_2") (pintype "passive"))
      (node (ref "XS2") (pin "1") (pinfunction "1_1") (pintype "passive"))
    )
    (net (code "38") (name "Net-(R39-Pad1)") (class "Default")
      (node (ref "R39") (pin "1") (pinfunction "1_1") (pintype "passive"))
      (node (ref "XP3") (pin "1") (pinfunction "1_1") (pintype "passive"))
    )
    (net (code "39") (name "Net-(R40-Pad1)") (class "Default")
      (node (ref "R40") (pin "1") (pinfunction "1_1") (pintype "passive"))
      (node (ref "XP3") (pin "7") (pinfunction "7_7") (pintype "passive"))
      (node (ref "XP3") (pin "8") (pinfunction "8_8") (pintype "passive"))
    )
    (net (code "40") (name "Net-(R40-Pad2)") (class "Default")
      (node (ref "R40") (pin "2") (pinfunction "2_2") (pintype "passive"))
      (node (ref "SW1") (pin "1") (pinfunction "1_1") (pintype "passive"))
    )
    (net (code "41") (name "Net-(R41-Pad1)") (class "Default")
      (node (ref "R41") (pin "1") (pinfunction "1_1") (pintype "passive"))
      (node (ref "XP3") (pin "4") (pinfunction "4_4") (pintype "passive"))
    )
    (net (code "42") (name "Net-(R42-Pad1)") (class "Default")
      (node (ref "R42") (pin "1") (pinfunction "1_1") (pintype "passive"))
      (node (ref "XP3") (pin "2") (pinfunction "2_2") (pintype "passive"))
    )
    (net (code "43") (name "Net-(SW1-Pad2)") (class "Default")
      (node (ref "SW1") (pin "2") (pinfunction "2_2") (pintype "passive"))
      (node (ref "XP3") (pin "10") (pinfunction "10_10") (pintype "passive"))
      (node (ref "XP3") (pin "9") (pinfunction "9_9") (pintype "passive"))
    )
    (net (code "44") (name "Net-(VD12-K)") (class "Default")
      (node (ref "R19") (pin "2") (pinfunction "2_2") (pintype "passive"))
      (node (ref "VD12") (pin "2") (pinfunction "K_2") (pintype "passive"))
    )
    (net (code "45") (name "Net-(VD13-K)") (class "Default")
      (node (ref "R21") (pin "2") (pinfunction "2_2") (pintype "passive"))
      (node (ref "VD13") (pin "2") (pinfunction "K_2") (pintype "passive"))
    )
    (net (code "46") (name "Net-(VD14-K)") (class "Default")
      (node (ref "R31") (pin "2") (pinfunction "2_2") (pintype "passive"))
      (node (ref "VD14") (pin "2") (pinfunction "K_2") (pintype "passive"))
    )
    (net (code "47") (name "Net-(VD17-K)") (class "Default")
      (node (ref "R33") (pin "2") (pinfunction "2_2") (pintype "passive"))
      (node (ref "VD17") (pin "2") (pinfunction "K_2") (pintype "passive"))
    )
    (net (code "48") (name "Net-(VD18-K)") (class "Default")
      (node (ref "R34") (pin "2") (pinfunction "2_2") (pintype "passive"))
      (node (ref "VD18") (pin "2") (pinfunction "K_2") (pintype "passive"))
    )
    (net (code "49") (name "Net-(VT1-B)") (class "Default")
      (node (ref "R24") (pin "1") (pinfunction "1_1") (pintype "passive"))
      (node (ref "R25") (pin "2") (pinfunction "2_2") (pintype "passive"))
      (node (ref "R26") (pin "2") (pinfunction "2_2") (pintype "passive"))
      (node (ref "VT1") (pin "1") (pinfunction "B_1") (pintype "passive"))
    )
    (net (code "50") (name "Net-(VT1-E)") (class "Default")
      (node (ref "R22") (pin "1") (pinfunction "1_1") (pintype "passive"))
      (node (ref "VT1") (pin "2") (pinfunction "E_2") (pintype "passive"))
    )
    (net (code "51") (name "Net-(XS1-D+)") (class "Default")
      (node (ref "R20") (pin "2") (pinfunction "2_2") (pintype "passive"))
      (node (ref "R22") (pin "2") (pinfunction "2_2") (pintype "passive"))
      (node (ref "XS1") (pin "3") (pinfunction "D+_3") (pintype "passive"))
    )
    (net (code "52") (name "Net-(XS1-D-)") (class "Default")
      (node (ref "R18") (pin "2") (pinfunction "2_2") (pintype "passive"))
      (node (ref "XS1") (pin "2") (pinfunction "D-_2") (pintype "passive"))
    )
    (net (code "53") (name "unconnected-(DD2-PA1-Pad11)") (class "Default")
      (node (ref "DD2") (pin "11") (pinfunction "PA1_11") (pintype "passive"))
    )
    (net (code "54") (name "unconnected-(DD2-PA4-Pad14)") (class "Default")
      (node (ref "DD2") (pin "14") (pinfunction "PA4_14") (pintype "passive"))
    )
    (net (code "55") (name "unconnected-(DD2-PA6-Pad16)") (class "Default")
      (node (ref "DD2") (pin "16") (pinfunction "PA6_16") (pintype "passive"))
    )
    (net (code "56") (name "unconnected-(DD2-PA7-Pad17)") (class "Default")
      (node (ref "DD2") (pin "17") (pinfunction "PA7_17") (pintype "passive"))
    )
    (net (code "57") (name "unconnected-(DD2-PA8-Pad29)") (class "Default")
      (node (ref "DD2") (pin "29") (pinfunction "PA8_29") (pintype "passive"))
    )
    (net (code "58") (name "unconnected-(DD2-PA9-Pad30)") (class "Default")
      (node (ref "DD2") (pin "30") (pinfunction "PA9_30") (pintype "passive"))
    )
    (net (code "59") (name "unconnected-(DD2-PA10-Pad31)") (class "Default")
      (node (ref "DD2") (pin "31") (pinfunction "PA10_31") (pintype "passive"))
    )
    (net (code "60") (name "unconnected-(DD2-PB1-Pad19)") (class "Default")
      (node (ref "DD2") (pin "19") (pinfunction "PB1_19") (pintype "passive"))
    )
    (net (code "61") (name "unconnected-(DD2-PB4{slash}JNTRST-Pad40)") (class "Default")
      (node (ref "DD2") (pin "40") (pinfunction "PB4/JNTRST_40") (pintype "passive"))
    )
    (net (code "62") (name "unconnected-(DD2-PB5-Pad41)") (class "Default")
      (node (ref "DD2") (pin "41") (pinfunction "PB5_41") (pintype "passive"))
    )
    (net (code "63") (name "unconnected-(DD2-PB6-Pad42)") (class "Default")
      (node (ref "DD2") (pin "42") (pinfunction "PB6_42") (pintype "passive"))
    )
    (net (code "64") (name "unconnected-(DD2-PB7-Pad43)") (class "Default")
      (node (ref "DD2") (pin "43") (pinfunction "PB7_43") (pintype "passive"))
    )
    (net (code "65") (name "unconnected-(DD2-PB8-Pad45)") (class "Default")
      (node (ref "DD2") (pin "45") (pinfunction "PB8_45") (pintype "passive"))
    )
    (net (code "66") (name "unconnected-(DD2-PB9-Pad46)") (class "Default")
      (node (ref "DD2") (pin "46") (pinfunction "PB9_46") (pintype "passive"))
    )
    (net (code "67") (name "unconnected-(DD2-PB10-Pad21)") (class "Default")
      (node (ref "DD2") (pin "21") (pinfunction "PB10_21") (pintype "passive"))
    )
    (net (code "68") (name "unconnected-(DD2-PB11-Pad22)") (class "Default")
      (node (ref "DD2") (pin "22") (pinfunction "PB11_22") (pintype "passive"))
    )
    (net (code "69") (name "unconnected-(DD2-PB15-Pad28)") (class "Default")
      (node (ref "DD2") (pin "28") (pinfunction "PB15_28") (pintype "passive"))
    )
    (net (code "70") (name "unconnected-(DD2-PC15-OSC32_OUT-Pad4)") (class "Default")
      (node (ref "DD2") (pin "4") (pinfunction "PC15-OSC32_OUT_4") (pintype "passive"))
    )
    (net (code "71") (name "unconnected-(DD4-nc-Pad1)") (class "Default")
      (node (ref "DD4") (pin "1") (pinfunction "nc_1") (pintype "passive"))
    )
    (net (code "72") (name "unconnected-(VD19-Pad3)") (class "Default")
      (node (ref "VD19") (pin "3") (pinfunction "3_3") (pintype "passive"))
    )
    (net (code "73") (name "unconnected-(XP3-Pad3)") (class "Default")
      (node (ref "XP3") (pin "3") (pinfunction "3_3") (pintype "passive"))
    )
    (net (code "74") (name "unconnected-(XP4-Pad6)") (class "Default")
      (node (ref "XP4") (pin "6") (pinfunction "6_6") (pintype "passive"))
    )
  )
)
